# avrdmx.net
KiCad netlist of a schematic drawn in EAGLE
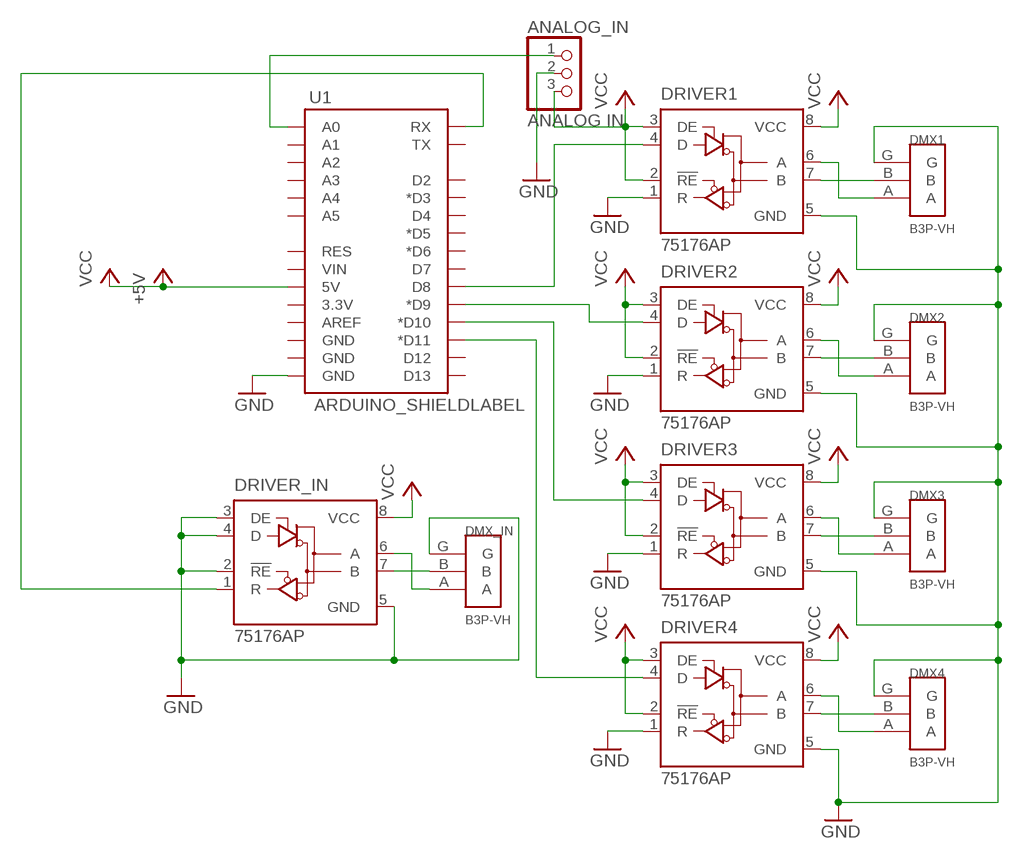
[diagram p0: schematic, sheet 1]

(export (version "E")
  (design (tool "Eeschema 10.0.6"))
  (components
    (comp (ref "ANALOG_IN")
      (value "ANALOG IN")
      (footprint "eagle-import:1X03")
      (libsource (lib "eagle-import") (part "PINHD-1X3"))
    )
    (comp (ref "DMX1")
      (value "B3P-VH")
      (footprint "eagle-import:B3P-VH")
      (libsource (lib "eagle-import") (part "B3P-VH"))
    )
    (comp (ref "DMX2")
      (value "B3P-VH")
      (footprint "eagle-import:B3P-VH")
      (libsource (lib "eagle-import") (part "B3P-VH"))
    )
    (comp (ref "DMX3")
      (value "B3P-VH")
      (footprint "eagle-import:B3P-VH")
      (libsource (lib "eagle-import") (part "B3P-VH"))
    )
    (comp (ref "DMX4")
      (value "B3P-VH")
      (footprint "eagle-import:B3P-VH")
      (libsource (lib "eagle-import") (part "B3P-VH"))
    )
    (comp (ref "DMX_IN")
      (value "B3P-VH")
      (footprint "eagle-import:B3P-VH")
      (libsource (lib "eagle-import") (part "B3P-VH"))
    )
    (comp (ref "DRIVER1")
      (value "75176AP")
      (footprint "eagle-import:DIL08")
      (libsource (lib "eagle-import") (part "75176AP"))
    )
    (comp (ref "DRIVER2")
      (value "75176AP")
      (footprint "eagle-import:DIL08")
      (libsource (lib "eagle-import") (part "75176AP"))
    )
    (comp (ref "DRIVER3")
      (value "75176AP")
      (footprint "eagle-import:DIL08")
      (libsource (lib "eagle-import") (part "75176AP"))
    )
    (comp (ref "DRIVER4")
      (value "75176AP")
      (footprint "eagle-import:DIL08")
      (libsource (lib "eagle-import") (part "75176AP"))
    )
    (comp (ref "DRIVER_IN")
      (value "75176AP")
      (footprint "eagle-import:DIL08")
      (libsource (lib "eagle-import") (part "75176AP"))
    )
    (comp (ref "U1")
      (value "ARDUINO_SHIELDLABEL")
      (footprint "eagle-import:DUEMILANOVE_SHIELD")
      (libsource (lib "eagle-import") (part "ARDUINO_SHIELDLABEL"))
    )
  )
  (nets
    (net (code "1") (name "+5V") (class "Default")
      (node (ref "ANALOG_IN") (pin "3") (pinfunction "3_3") (pintype "passive"))
      (node (ref "DRIVER1") (pin "2") (pinfunction "~{RE}_2") (pintype "input"))
      (node (ref "DRIVER1") (pin "3") (pinfunction "DE_3") (pintype "input"))
      (node (ref "DRIVER1") (pin "8") (pinfunction "VCC_8") (pintype "power_in"))
      (node (ref "DRIVER2") (pin "2") (pinfunction "~{RE}_2") (pintype "input"))
      (node (ref "DRIVER2") (pin "3") (pinfunction "DE_3") (pintype "input"))
      (node (ref "DRIVER2") (pin "8") (pinfunction "VCC_8") (pintype "power_in"))
      (node (ref "DRIVER3") (pin "2") (pinfunction "~{RE}_2") (pintype "input"))
      (node (ref "DRIVER3") (pin "3") (pinfunction "DE_3") (pintype "input"))
      (node (ref "DRIVER3") (pin "8") (pinfunction "VCC_8") (pintype "power_in"))
      (node (ref "DRIVER4") (pin "2") (pinfunction "~{RE}_2") (pintype "input"))
      (node (ref "DRIVER4") (pin "3") (pinfunction "DE_3") (pintype "input"))
      (node (ref "DRIVER4") (pin "8") (pinfunction "VCC_8") (pintype "power_in"))
      (node (ref "DRIVER_IN") (pin "8") (pinfunction "VCC_8") (pintype "power_in"))
      (node (ref "U1") (pin "5V") (pinfunction "5V_5V") (pintype "bidirectional"))
    )
    (net (code "2") (name "GND") (class "Default")
      (node (ref "ANALOG_IN") (pin "2") (pinfunction "2_2") (pintype "passive"))
      (node (ref "DMX1") (pin "G") (pinfunction "G_G") (pintype "bidirectional"))
      (node (ref "DMX2") (pin "G") (pinfunction "G_G") (pintype "bidirectional"))
      (node (ref "DMX3") (pin "G") (pinfunction "G_G") (pintype "bidirectional"))
      (node (ref "DMX4") (pin "G") (pinfunction "G_G") (pintype "bidirectional"))
      (node (ref "DMX_IN") (pin "G") (pinfunction "G_G") (pintype "bidirectional"))
      (node (ref "DRIVER1") (pin "1") (pinfunction "R_1") (pintype "input"))
      (node (ref "DRIVER1") (pin "5") (pinfunction "GND_5") (pintype "power_in"))
      (node (ref "DRIVER2") (pin "1") (pinfunction "R_1") (pintype "input"))
      (node (ref "DRIVER2") (pin "5") (pinfunction "GND_5") (pintype "power_in"))
      (node (ref "DRIVER3") (pin "1") (pinfunction "R_1") (pintype "input"))
      (node (ref "DRIVER3") (pin "5") (pinfunction "GND_5") (pintype "power_in"))
      (node (ref "DRIVER4") (pin "1") (pinfunction "R_1") (pintype "input"))
      (node (ref "DRIVER4") (pin "5") (pinfunction "GND_5") (pintype "power_in"))
      (node (ref "DRIVER_IN") (pin "2") (pinfunction "~{RE}_2") (pintype "input"))
      (node (ref "DRIVER_IN") (pin "3") (pinfunction "DE_3") (pintype "input"))
      (node (ref "DRIVER_IN") (pin "4") (pinfunction "D_4") (pintype "input"))
      (node (ref "DRIVER_IN") (pin "5") (pinfunction "GND_5") (pintype "power_in"))
      (node (ref "U1") (pin "GND@0") (pinfunction "GND_GND@0") (pintype "bidirectional"))
    )
    (net (code "3") (name "Net-(ANALOG_IN-Pad1)") (class "Default")
      (node (ref "ANALOG_IN") (pin "1") (pinfunction "1_1") (pintype "passive"))
      (node (ref "U1") (pin "A0") (pinfunction "A0_A0") (pintype "bidirectional"))
    )
    (net (code "4") (name "Net-(DRIVER1-A)") (class "Default")
      (node (ref "DMX1") (pin "A") (pinfunction "A_A") (pintype "bidirectional"))
      (node (ref "DRIVER1") (pin "6") (pinfunction "A_6") (pintype "output"))
    )
    (net (code "5") (name "Net-(DRIVER1-B)") (class "Default")
      (node (ref "DMX1") (pin "B") (pinfunction "B_B") (pintype "bidirectional"))
      (node (ref "DRIVER1") (pin "7") (pinfunction "B_7") (pintype "output"))
    )
    (net (code "6") (name "Net-(DRIVER1-D)") (class "Default")
      (node (ref "DRIVER1") (pin "4") (pinfunction "D_4") (pintype "input"))
      (node (ref "U1") (pin "D8") (pinfunction "D8_D8") (pintype "bidirectional"))
    )
    (net (code "7") (name "Net-(DRIVER2-A)") (class "Default")
      (node (ref "DMX2") (pin "A") (pinfunction "A_A") (pintype "bidirectional"))
      (node (ref "DRIVER2") (pin "6") (pinfunction "A_6") (pintype "output"))
    )
    (net (code "8") (name "Net-(DRIVER2-B)") (class "Default")
      (node (ref "DMX2") (pin "B") (pinfunction "B_B") (pintype "bidirectional"))
      (node (ref "DRIVER2") (pin "7") (pinfunction "B_7") (pintype "output"))
    )
    (net (code "9") (name "Net-(DRIVER2-D)") (class "Default")
      (node (ref "DRIVER2") (pin "4") (pinfunction "D_4") (pintype "input"))
      (node (ref "U1") (pin "D9") (pinfunction "*D9_D9") (pintype "bidirectional"))
    )
    (net (code "10") (name "Net-(DRIVER3-A)") (class "Default")
      (node (ref "DMX3") (pin "A") (pinfunction "A_A") (pintype "bidirectional"))
      (node (ref "DRIVER3") (pin "6") (pinfunction "A_6") (pintype "output"))
    )
    (net (code "11") (name "Net-(DRIVER3-B)") (class "Default")
      (node (ref "DMX3") (pin "B") (pinfunction "B_B") (pintype "bidirectional"))
      (node (ref "DRIVER3") (pin "7") (pinfunction "B_7") (pintype "output"))
    )
    (net (code "12") (name "Net-(DRIVER3-D)") (class "Default")
      (node (ref "DRIVER3") (pin "4") (pinfunction "D_4") (pintype "input"))
      (node (ref "U1") (pin "D10") (pinfunction "*D10_D10") (pintype "bidirectional"))
    )
    (net (code "13") (name "Net-(DRIVER4-A)") (class "Default")
      (node (ref "DMX4") (pin "A") (pinfunction "A_A") (pintype "bidirectional"))
      (node (ref "DRIVER4") (pin "6") (pinfunction "A_6") (pintype "output"))
    )
    (net (code "14") (name "Net-(DRIVER4-B)") (class "Default")
      (node (ref "DMX4") (pin "B") (pinfunction "B_B") (pintype "bidirectional"))
      (node (ref "DRIVER4") (pin "7") (pinfunction "B_7") (pintype "output"))
    )
    (net (code "15") (name "Net-(DRIVER4-D)") (class "Default")
      (node (ref "DRIVER4") (pin "4") (pinfunction "D_4") (pintype "input"))
      (node (ref "U1") (pin "D11") (pinfunction "*D11_D11") (pintype "bidirectional"))
    )
    (net (code "16") (name "Net-(DRIVER_IN-A)") (class "Default")
      (node (ref "DMX_IN") (pin "A") (pinfunction "A_A") (pintype "bidirectional"))
      (node (ref "DRIVER_IN") (pin "6") (pinfunction "A_6") (pintype "output"))
    )
    (net (code "17") (name "Net-(DRIVER_IN-B)") (class "Default")
      (node (ref "DMX_IN") (pin "B") (pinfunction "B_B") (pintype "bidirectional"))
      (node (ref "DRIVER_IN") (pin "7") (pinfunction "B_7") (pintype "output"))
    )
    (net (code "18") (name "Net-(DRIVER_IN-R)") (class "Default")
      (node (ref "DRIVER_IN") (pin "1") (pinfunction "R_1") (pintype "input"))
      (node (ref "U1") (pin "RX") (pinfunction "RX_RX") (pintype "bidirectional"))
    )
    (net (code "19") (name "unconnected-(U1-*D3-PadD3)") (class "Default")
      (node (ref "U1") (pin "D3") (pinfunction "*D3_D3") (pintype "bidirectional"))
    )
    (net (code "20") (name "unconnected-(U1-*D5-PadD5)") (class "Default")
      (node (ref "U1") (pin "D5") (pinfunction "*D5_D5") (pintype "bidirectional"))
    )
    (net (code "21") (name "unconnected-(U1-*D6-PadD6)") (class "Default")
      (node (ref "U1") (pin "D6") (pinfunction "*D6_D6") (pintype "bidirectional"))
    )
    (net (code "22") (name "unconnected-(U1-GND-PadGND@1)") (class "Default")
      (node (ref "U1") (pin "GND@1") (pinfunction "GND_GND@1") (pintype "bidirectional"))
    )
    (net (code "23") (name "unconnected-(U1-GND-PadGND@2)") (class "Default")
      (node (ref "U1") (pin "GND@2") (pinfunction "GND_GND@2") (pintype "bidirectional"))
    )
    (net (code "24") (name "unconnected-(U1-Pad3.3V)") (class "Default")
      (node (ref "U1") (pin "3.3V") (pinfunction "3.3V_3.3V") (pintype "bidirectional"))
    )
    (net (code "25") (name "unconnected-(U1-PadA1)") (class "Default")
      (node (ref "U1") (pin "A1") (pinfunction "A1_A1") (pintype "bidirectional"))
    )
    (net (code "26") (name "unconnected-(U1-PadA2)") (class "Default")
      (node (ref "U1") (pin "A2") (pinfunction "A2_A2") (pintype "bidirectional"))
    )
    (net (code "27") (name "unconnected-(U1-PadA3)") (class "Default")
      (node (ref "U1") (pin "A3") (pinfunction "A3_A3") (pintype "bidirectional"))
    )
    (net (code "28") (name "unconnected-(U1-PadA4)") (class "Default")
      (node (ref "U1") (pin "A4") (pinfunction "A4_A4") (pintype "bidirectional"))
    )
    (net (code "29") (name "unconnected-(U1-PadA5)") (class "Default")
      (node (ref "U1") (pin "A5") (pinfunction "A5_A5") (pintype "bidirectional"))
    )
    (net (code "30") (name "unconnected-(U1-PadAREF)") (class "Default")
      (node (ref "U1") (pin "AREF") (pinfunction "AREF_AREF") (pintype "bidirectional"))
    )
    (net (code "31") (name "unconnected-(U1-PadD2)") (class "Default")
      (node (ref "U1") (pin "D2") (pinfunction "D2_D2") (pintype "bidirectional"))
    )
    (net (code "32") (name "unconnected-(U1-PadD4)") (class "Default")
      (node (ref "U1") (pin "D4") (pinfunction "D4_D4") (pintype "bidirectional"))
    )
    (net (code "33") (name "unconnected-(U1-PadD7)") (class "Default")
      (node (ref "U1") (pin "D7") (pinfunction "D7_D7") (pintype "bidirectional"))
    )
    (net (code "34") (name "unconnected-(U1-PadD12)") (class "Default")
      (node (ref "U1") (pin "D12") (pinfunction "D12_D12") (pintype "bidirectional"))
    )
    (net (code "35") (name "unconnected-(U1-PadD13)") (class "Default")
      (node (ref "U1") (pin "D13") (pinfunction "D13_D13") (pintype "bidirectional"))
    )
    (net (code "36") (name "unconnected-(U1-PadRES)") (class "Default")
      (node (ref "U1") (pin "RES") (pinfunction "RES_RES") (pintype "bidirectional"))
    )
    (net (code "37") (name "unconnected-(U1-PadTX)") (class "Default")
      (node (ref "U1") (pin "TX") (pinfunction "TX_TX") (pintype "bidirectional"))
    )
    (net (code "38") (name "unconnected-(U1-PadVIN)") (class "Default")
      (node (ref "U1") (pin "VIN") (pinfunction "VIN_VIN") (pintype "bidirectional"))
    )
  )
)
